# BIRDS-5_FM__Y_Panel_Ver2.net
KiCad netlist of a schematic drawn in EAGLE
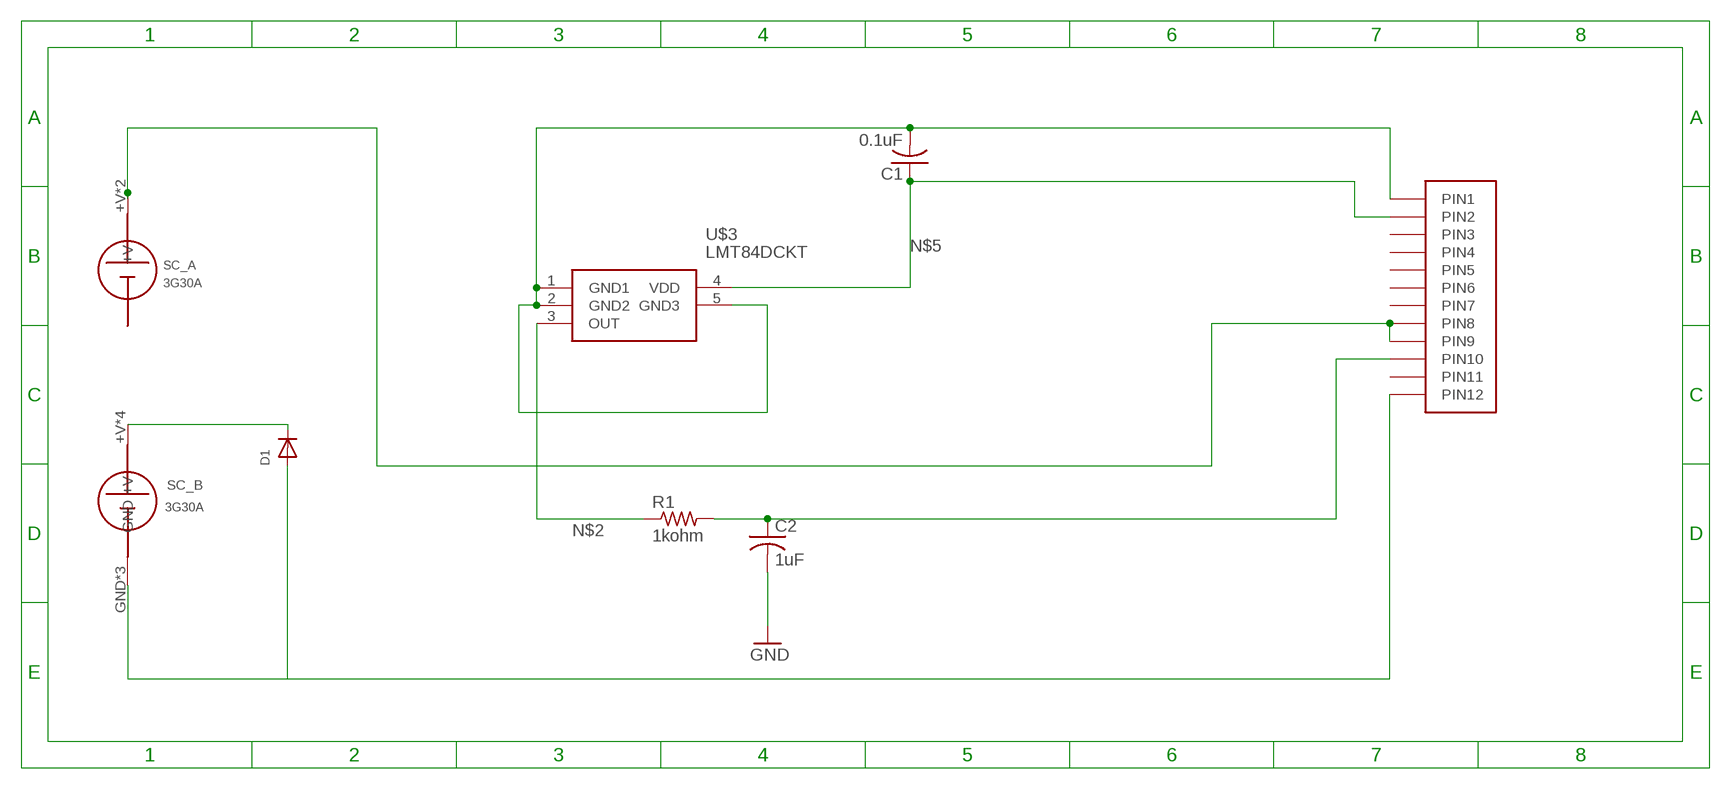
[diagram p0: schematic, sheet 1]

(export (version "E")
  (design (tool "Eeschema 10.0.6"))
  (components
    (comp (ref "C1")
      (value "0.1uF")
      (footprint "eagle-import:C0805")
      (libsource (lib "eagle-import") (part "C-USC0805"))
    )
    (comp (ref "C2")
      (value "1uF")
      (footprint "eagle-import:C0805")
      (libsource (lib "eagle-import") (part "C-USC0805"))
    )
    (comp (ref "D1")
      (value "DIODE_SOD-123FL")
      (footprint "eagle-import:SOD-123FL")
      (libsource (lib "eagle-import") (part "DIODE_SOD-123FL"))
    )
    (comp (ref "R1")
      (value "1kohm")
      (footprint "eagle-import:R0402")
      (libsource (lib "eagle-import") (part "R-US_R0402"))
    )
    (comp (ref "SOLARCELL_A")
      (value "SC_A")
      (footprint "eagle-import:SC_A")
      (libsource (lib "eagle-import") (part "SC_A"))
    )
    (comp (ref "U$1")
      (value "HEADER12PIN")
      (footprint "eagle-import:HEADER12PIN")
      (libsource (lib "eagle-import") (part "HEADER12PIN"))
    )
    (comp (ref "U$2")
      (value "SC_B-2_SC_B")
      (footprint "eagle-import:SC_B-2_SC_B")
      (libsource (lib "eagle-import") (part "SC_B-2_SC_B"))
    )
    (comp (ref "U$3")
      (value "LMT84DCKT")
      (footprint "eagle-import:SOT65P210X110-5N")
      (fields (field (name "RS_PART_NUMBER") "8115860"))
      (libsource (lib "eagle-import") (part "LMT84DCKT"))
    )
  )
  (nets
    (net (code "1") (name "/N$2") (class "Default")
      (node (ref "R1") (pin "1") (pinfunction "1_1") (pintype "passive"))
      (node (ref "U$3") (pin "3") (pinfunction "OUT_3") (pintype "output"))
    )
    (net (code "2") (name "/N$5") (class "Default")
      (node (ref "C1") (pin "1") (pinfunction "1_1") (pintype "passive"))
      (node (ref "U$1") (pin "P2") (pinfunction "PIN2_P2") (pintype "bidirectional"))
      (node (ref "U$3") (pin "4") (pinfunction "VDD_4") (pintype "power_in"))
    )
    (net (code "3") (name "GND") (class "Default")
      (node (ref "C1") (pin "2") (pinfunction "2_2") (pintype "passive"))
      (node (ref "C2") (pin "2") (pinfunction "2_2") (pintype "passive"))
      (node (ref "D1") (pin "A") (pinfunction "A_A") (pintype "passive"))
      (node (ref "U$1") (pin "P1") (pinfunction "PIN1_P1") (pintype "bidirectional"))
      (node (ref "U$1") (pin "P12") (pinfunction "PIN12_P12") (pintype "bidirectional"))
      (node (ref "U$2") (pin "GND") (pinfunction "GND_GND") (pintype "bidirectional"))
      (node (ref "U$2") (pin "GND1") (pinfunction "GND_GND1") (pintype "bidirectional"))
      (node (ref "U$2") (pin "GND2") (pinfunction "GND_GND2") (pintype "bidirectional"))
      (node (ref "U$3") (pin "1") (pinfunction "GND1_1") (pintype "power_in"))
      (node (ref "U$3") (pin "2") (pinfunction "GND2_2") (pintype "power_in"))
      (node (ref "U$3") (pin "5") (pinfunction "GND3_5") (pintype "power_in"))
    )
    (net (code "4") (name "Net-(D1-PadC)") (class "Default")
      (node (ref "D1") (pin "C") (pinfunction "C_C") (pintype "passive"))
      (node (ref "U$2") (pin "+V") (pinfunction "+V_+V") (pintype "bidirectional"))
      (node (ref "U$2") (pin "+V2") (pinfunction "+V_+V2") (pintype "bidirectional"))
      (node (ref "U$2") (pin "+V3") (pinfunction "+V_+V3") (pintype "bidirectional"))
      (node (ref "U$2") (pin "+V4") (pinfunction "+V_+V4") (pintype "bidirectional"))
    )
    (net (code "5") (name "Net-(U$1-PIN8)") (class "Default")
      (node (ref "SOLARCELL_A") (pin "+V") (pinfunction "+V_+V") (pintype "bidirectional"))
      (node (ref "SOLARCELL_A") (pin "+V1") (pinfunction "+V_+V1") (pintype "bidirectional"))
      (node (ref "U$1") (pin "P8") (pinfunction "PIN8_P8") (pintype "bidirectional"))
      (node (ref "U$1") (pin "P9") (pinfunction "PIN9_P9") (pintype "bidirectional"))
    )
    (net (code "6") (name "Net-(U$1-PIN10)") (class "Default")
      (node (ref "C2") (pin "1") (pinfunction "1_1") (pintype "passive"))
      (node (ref "R1") (pin "2") (pinfunction "2_2") (pintype "passive"))
      (node (ref "U$1") (pin "P10") (pinfunction "PIN10_P10") (pintype "bidirectional"))
    )
    (net (code "7") (name "unconnected-(U$1-PIN3-PadP3)") (class "Default")
      (node (ref "U$1") (pin "P3") (pinfunction "PIN3_P3") (pintype "bidirectional"))
    )
    (net (code "8") (name "unconnected-(U$1-PIN4-PadP4)") (class "Default")
      (node (ref "U$1") (pin "P4") (pinfunction "PIN4_P4") (pintype "bidirectional"))
    )
    (net (code "9") (name "unconnected-(U$1-PIN5-PadP5)") (class "Default")
      (node (ref "U$1") (pin "P5") (pinfunction "PIN5_P5") (pintype "bidirectional"))
    )
    (net (code "10") (name "unconnected-(U$1-PIN6-PadP6)") (class "Default")
      (node (ref "U$1") (pin "P6") (pinfunction "PIN6_P6") (pintype "bidirectional"))
    )
    (net (code "11") (name "unconnected-(U$1-PIN7-PadP7)") (class "Default")
      (node (ref "U$1") (pin "P7") (pinfunction "PIN7_P7") (pintype "bidirectional"))
    )
    (net (code "12") (name "unconnected-(U$1-PIN11-PadP11)") (class "Default")
      (node (ref "U$1") (pin "P11") (pinfunction "PIN11_P11") (pintype "bidirectional"))
    )
  )
)
